# shift_reg_breakout.net
KiCad netlist of a schematic drawn in Altium Designer
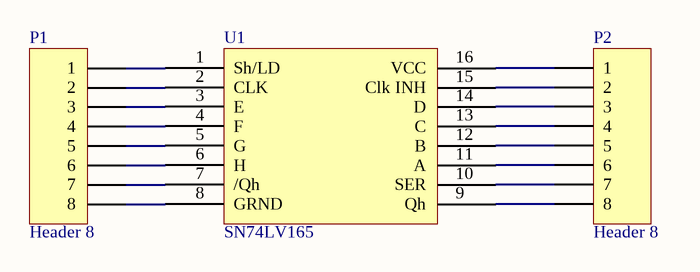
[diagram p0: shift_reg_breakout.SchDoc]

(export (version "E")
  (design (tool "Eeschema 10.0.6"))
  (components
    (comp (ref "P1")
      (value "Header 8")
      (footprint "HDR1X8")
      (description "Header, 8-Pin")
      (fields (field (name "PUBLISHER") "Altium Limited"))
      (libsource (lib "") (part "Header 8_1"))
    )
    (comp (ref "P2")
      (value "Header 8")
      (footprint "HDR1X8")
      (description "Header, 8-Pin")
      (fields (field (name "PUBLISHER") "Altium Limited"))
      (libsource (lib "Miscellaneous Connectors") (part "Header 8"))
    )
    (comp (ref "U1")
      (value "SN74LV165")
      (footprint "SOP16_Hand")
      (libsource (lib "GameMan") (part "SN74LV165"))
    )
  )
  (nets
    (net (code "1") (name "Net-(U1-A)") (class "Default")
      (node (ref "P2") (pin "6") (pinfunction "6_6") (pintype "passive"))
      (node (ref "U1") (pin "11") (pinfunction "A_11") (pintype "passive"))
    )
    (net (code "2") (name "Net-(U1-B)") (class "Default")
      (node (ref "P2") (pin "5") (pinfunction "5_5") (pintype "passive"))
      (node (ref "U1") (pin "12") (pinfunction "B_12") (pintype "passive"))
    )
    (net (code "3") (name "Net-(U1-C)") (class "Default")
      (node (ref "P2") (pin "4") (pinfunction "4_4") (pintype "passive"))
      (node (ref "U1") (pin "13") (pinfunction "C_13") (pintype "passive"))
    )
    (net (code "4") (name "Net-(U1-CLK)") (class "Default")
      (node (ref "P1") (pin "2") (pinfunction "2_2") (pintype "passive"))
      (node (ref "U1") (pin "2") (pinfunction "CLK_2") (pintype "passive"))
    )
    (net (code "5") (name "Net-(U1-Clk_INH)") (class "Default")
      (node (ref "P2") (pin "2") (pinfunction "2_2") (pintype "passive"))
      (node (ref "U1") (pin "15") (pinfunction "Clk_INH_15") (pintype "passive"))
    )
    (net (code "6") (name "Net-(U1-D)") (class "Default")
      (node (ref "P2") (pin "3") (pinfunction "3_3") (pintype "passive"))
      (node (ref "U1") (pin "14") (pinfunction "D_14") (pintype "passive"))
    )
    (net (code "7") (name "Net-(U1-E)") (class "Default")
      (node (ref "P1") (pin "3") (pinfunction "3_3") (pintype "passive"))
      (node (ref "U1") (pin "3") (pinfunction "E_3") (pintype "passive"))
    )
    (net (code "8") (name "Net-(U1-F)") (class "Default")
      (node (ref "P1") (pin "4") (pinfunction "4_4") (pintype "passive"))
      (node (ref "U1") (pin "4") (pinfunction "F_4") (pintype "passive"))
    )
    (net (code "9") (name "Net-(U1-G)") (class "Default")
      (node (ref "P1") (pin "5") (pinfunction "5_5") (pintype "passive"))
      (node (ref "U1") (pin "5") (pinfunction "G_5") (pintype "passive"))
    )
    (net (code "10") (name "Net-(U1-GRND)") (class "Default")
      (node (ref "P1") (pin "8") (pinfunction "8_8") (pintype "passive"))
      (node (ref "U1") (pin "8") (pinfunction "GRND_8") (pintype "passive"))
    )
    (net (code "11") (name "Net-(U1-H)") (class "Default")
      (node (ref "P1") (pin "6") (pinfunction "6_6") (pintype "passive"))
      (node (ref "U1") (pin "6") (pinfunction "H_6") (pintype "passive"))
    )
    (net (code "12") (name "Net-(U1-Qh)") (class "Default")
      (node (ref "P2") (pin "8") (pinfunction "8_8") (pintype "passive"))
      (node (ref "U1") (pin "9") (pinfunction "Qh_9") (pintype "passive"))
    )
    (net (code "13") (name "Net-(U1-SER)") (class "Default")
      (node (ref "P2") (pin "7") (pinfunction "7_7") (pintype "passive"))
      (node (ref "U1") (pin "10") (pinfunction "SER_10") (pintype "passive"))
    )
    (net (code "14") (name "Net-(U1-Sh{slash}LD)") (class "Default")
      (node (ref "P1") (pin "1") (pinfunction "1_1") (pintype "passive"))
      (node (ref "U1") (pin "1") (pinfunction "Sh/LD_1") (pintype "passive"))
    )
    (net (code "15") (name "Net-(U1-VCC)") (class "Default")
      (node (ref "P2") (pin "1") (pinfunction "1_1") (pintype "passive"))
      (node (ref "U1") (pin "16") (pinfunction "VCC_16") (pintype "passive"))
    )
    (net (code "16") (name "Net-(U1-{slash}Qh)") (class "Default")
      (node (ref "P1") (pin "7") (pinfunction "7_7") (pintype "passive"))
      (node (ref "U1") (pin "7") (pinfunction "/Qh_7") (pintype "passive"))
    )
  )
)
